# untitled.net
KiCad netlist of a schematic drawn in EAGLE
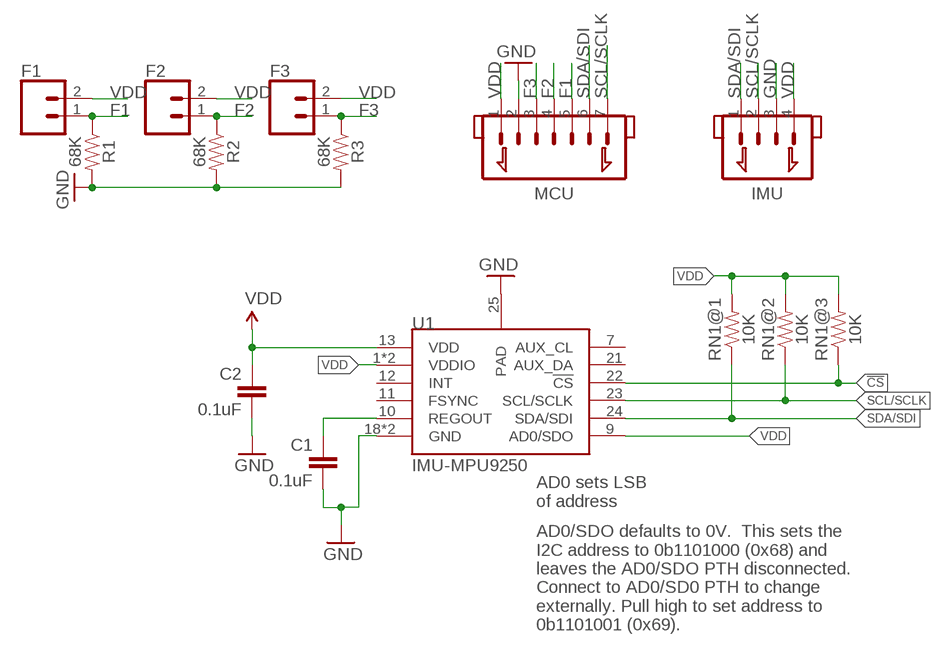
[diagram p0: schematic, sheet 1]

(export (version "E")
  (design (tool "Eeschema 10.0.6"))
  (components
    (comp (ref "C1")
      (value "0.1uF")
      (footprint "eagle-import:0603-CAP")
      (libsource (lib "eagle-import") (part "0.1UF-25V(+80/-20%)(0603)"))
    )
    (comp (ref "C2")
      (value "0.1uF")
      (footprint "eagle-import:0603-CAP")
      (libsource (lib "eagle-import") (part "0.1UF-25V(+80/-20%)(0603)"))
    )
    (comp (ref "F1")
      (value "CONN_02LOCK_LONGPADS")
      (footprint "eagle-import:1X02_LOCK_LONGPADS")
      (libsource (lib "eagle-import") (part "CONN_02LOCK_LONGPADS"))
    )
    (comp (ref "F2")
      (value "CONN_02LOCK_LONGPADS")
      (footprint "eagle-import:1X02_LOCK_LONGPADS")
      (libsource (lib "eagle-import") (part "CONN_02LOCK_LONGPADS"))
    )
    (comp (ref "F3")
      (value "CONN_02LOCK_LONGPADS")
      (footprint "eagle-import:1X02_LOCK_LONGPADS")
      (libsource (lib "eagle-import") (part "CONN_02LOCK_LONGPADS"))
    )
    (comp (ref "IMU")
      (value "JST_1.25_4P")
      (footprint "eagle-import:JST1.25_4P")
      (libsource (lib "eagle-import") (part "JST_1.25_4P"))
    )
    (comp (ref "MCU")
      (value "JST_1.25_7P")
      (footprint "eagle-import:JST1.25_7P")
      (libsource (lib "eagle-import") (part "JST_1.25_7P"))
    )
    (comp (ref "R1")
      (value "68K")
      (footprint "eagle-import:0603")
      (libsource (lib "eagle-import") (part "RESISTOR0603"))
    )
    (comp (ref "R2")
      (value "68K")
      (footprint "eagle-import:0603")
      (libsource (lib "eagle-import") (part "RESISTOR0603"))
    )
    (comp (ref "R3")
      (value "68K")
      (footprint "eagle-import:0603")
      (libsource (lib "eagle-import") (part "RESISTOR0603"))
    )
    (comp (ref "RN1")
      (value "10K")
      (footprint "eagle-import:RESCAF80P320X160X60-8N")
      (libsource (lib "eagle-import") (part "RESISTOR_ARRAY_1206_SEPARATE"))
    )
    (comp (ref "U1")
      (value "IMU-MPU9250")
      (footprint "eagle-import:LEAD-QFN24")
      (libsource (lib "eagle-import") (part "IMU-MPU9250"))
    )
  )
  (nets
    (net (code "1") (name "/F1") (class "Default")
      (node (ref "F1") (pin "1") (pinfunction "1_1") (pintype "passive"))
      (node (ref "MCU") (pin "5") (pinfunction "5_5") (pintype "passive"))
      (node (ref "R1") (pin "1") (pinfunction "1_1") (pintype "passive"))
    )
    (net (code "2") (name "/F2") (class "Default")
      (node (ref "F2") (pin "1") (pinfunction "1_1") (pintype "passive"))
      (node (ref "MCU") (pin "4") (pinfunction "4_4") (pintype "passive"))
      (node (ref "R2") (pin "1") (pinfunction "1_1") (pintype "passive"))
    )
    (net (code "3") (name "/F3") (class "Default")
      (node (ref "F3") (pin "1") (pinfunction "1_1") (pintype "passive"))
      (node (ref "MCU") (pin "3") (pinfunction "3_3") (pintype "passive"))
      (node (ref "R3") (pin "1") (pinfunction "1_1") (pintype "passive"))
    )
    (net (code "4") (name "/~{CS}") (class "Default")
      (node (ref "RN1") (pin "3") (pinfunction "1_3") (pintype "passive"))
      (node (ref "U1") (pin "22") (pinfunction "~{CS}_22") (pintype "bidirectional"))
    )
    (net (code "5") (name "GND") (class "Default")
      (node (ref "C1") (pin "2") (pinfunction "2_2") (pintype "passive"))
      (node (ref "C2") (pin "2") (pinfunction "2_2") (pintype "passive"))
      (node (ref "IMU") (pin "3") (pinfunction "3_3") (pintype "passive"))
      (node (ref "MCU") (pin "2") (pinfunction "2_2") (pintype "passive"))
      (node (ref "R1") (pin "2") (pinfunction "2_2") (pintype "passive"))
      (node (ref "R2") (pin "2") (pinfunction "2_2") (pintype "passive"))
      (node (ref "R3") (pin "2") (pinfunction "2_2") (pintype "passive"))
      (node (ref "U1") (pin "18") (pinfunction "GND_18") (pintype "bidirectional"))
      (node (ref "U1") (pin "20") (pinfunction "GND_20") (pintype "bidirectional"))
      (node (ref "U1") (pin "25") (pinfunction "PAD_25") (pintype "bidirectional"))
    )
    (net (code "6") (name "Net-(U1-REGOUT)") (class "Default")
      (node (ref "C1") (pin "1") (pinfunction "1_1") (pintype "passive"))
      (node (ref "U1") (pin "10") (pinfunction "REGOUT_10") (pintype "bidirectional"))
    )
    (net (code "7") (name "SCL{slash}SCLK") (class "Default")
      (node (ref "IMU") (pin "2") (pinfunction "2_2") (pintype "passive"))
      (node (ref "MCU") (pin "7") (pinfunction "7_7") (pintype "passive"))
      (node (ref "RN1") (pin "2") (pinfunction "1_2") (pintype "passive"))
      (node (ref "U1") (pin "23") (pinfunction "SCL/SCLK_23") (pintype "bidirectional"))
    )
    (net (code "8") (name "SDA{slash}SDI") (class "Default")
      (node (ref "IMU") (pin "1") (pinfunction "1_1") (pintype "passive"))
      (node (ref "MCU") (pin "6") (pinfunction "6_6") (pintype "passive"))
      (node (ref "RN1") (pin "1") (pinfunction "1_1") (pintype "passive"))
      (node (ref "U1") (pin "24") (pinfunction "SDA/SDI_24") (pintype "bidirectional"))
    )
    (net (code "9") (name "VDD") (class "Default")
      (node (ref "C2") (pin "1") (pinfunction "1_1") (pintype "passive"))
      (node (ref "F1") (pin "2") (pinfunction "2_2") (pintype "passive"))
      (node (ref "F2") (pin "2") (pinfunction "2_2") (pintype "passive"))
      (node (ref "F3") (pin "2") (pinfunction "2_2") (pintype "passive"))
      (node (ref "IMU") (pin "4") (pinfunction "4_4") (pintype "passive"))
      (node (ref "MCU") (pin "1") (pinfunction "1_1") (pintype "passive"))
      (node (ref "RN1") (pin "6") (pinfunction "2_6") (pintype "passive"))
      (node (ref "RN1") (pin "7") (pinfunction "2_7") (pintype "passive"))
      (node (ref "RN1") (pin "8") (pinfunction "2_8") (pintype "passive"))
      (node (ref "U1") (pin "1") (pinfunction "VDDIO_1") (pintype "bidirectional"))
      (node (ref "U1") (pin "13") (pinfunction "VDD_13") (pintype "bidirectional"))
      (node (ref "U1") (pin "8") (pinfunction "VDDIO_8") (pintype "bidirectional"))
      (node (ref "U1") (pin "9") (pinfunction "AD0/SDO_9") (pintype "bidirectional"))
    )
    (net (code "10") (name "unconnected-(U1-AUX_CL-Pad7)") (class "Default")
      (node (ref "U1") (pin "7") (pinfunction "AUX_CL_7") (pintype "bidirectional"))
    )
    (net (code "11") (name "unconnected-(U1-AUX_DA-Pad21)") (class "Default")
      (node (ref "U1") (pin "21") (pinfunction "AUX_DA_21") (pintype "bidirectional"))
    )
    (net (code "12") (name "unconnected-(U1-FSYNC-Pad11)") (class "Default")
      (node (ref "U1") (pin "11") (pinfunction "FSYNC_11") (pintype "bidirectional"))
    )
    (net (code "13") (name "unconnected-(U1-INT-Pad12)") (class "Default")
      (node (ref "U1") (pin "12") (pinfunction "INT_12") (pintype "bidirectional"))
    )
  )
)
